# Arduino_Uno_R3_CP.net
KiCad netlist of a schematic drawn in Altium Designer
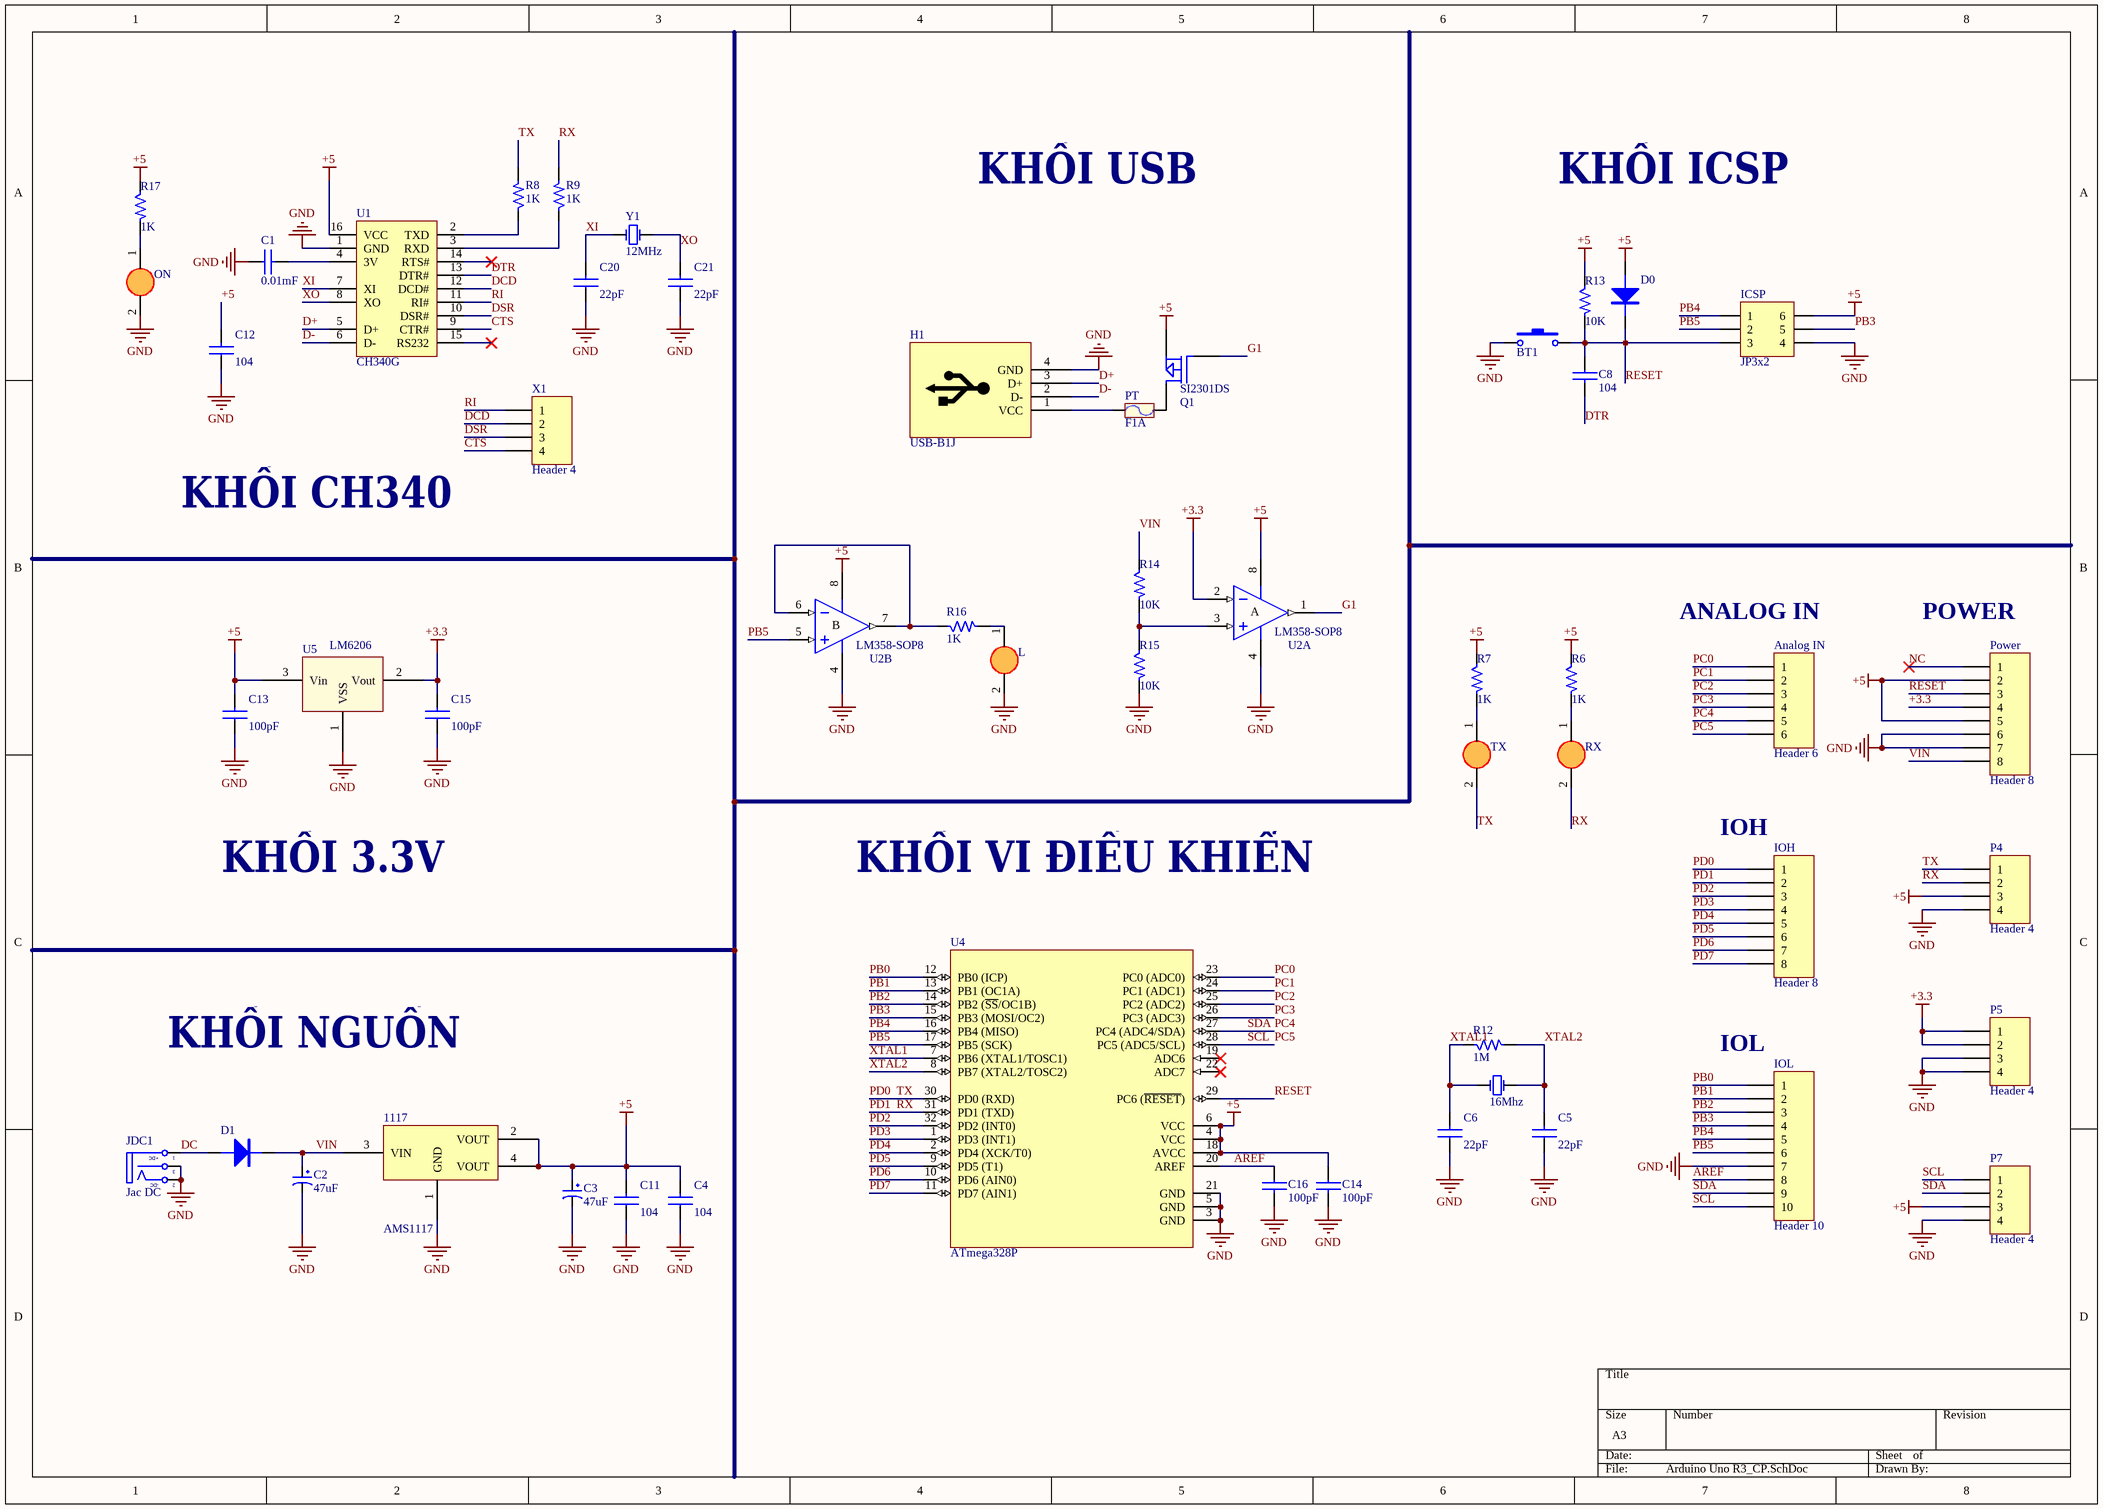
[diagram p0: Arduino Uno R3_CP.SchDoc]

(export (version "E")
  (design (tool "Eeschema 10.0.6"))
  (components
    (comp (ref "1117")
      (value "AMS1117")
      (footprint "SOT223-4N")
      (description "AMS")
      (libsource (lib "Thu Vien Chuan MH") (part "AMS1117"))
    )
    (comp (ref "Analog IN")
      (value "Header 6")
      (footprint "JP6-C1T")
      (description "Header, 6-Pin")
      (fields (field (name "PUBLISHER") "Altium Limited"))
      (libsource (lib "Miscellaneous Connectors") (part "Header 6"))
    )
    (comp (ref "BT1")
      (value "Nut Nhan 2 Chan")
      (footprint "BT 4 PIN 6.2*6.2*3.1")
      (fields (field (name "PUBLISHER") "Altium Limited"))
      (libsource (lib "Thu Vien Chuan MH") (part "Nut Nhan 2 Chan"))
    )
    (comp (ref "C1")
      (value "0.01mF")
      (footprint "CN-SMD-0805")
      (description "Tu 0805")
      (libsource (lib "Thu Vien Chuan MH") (part "Tu 0805"))
    )
    (comp (ref "C2")
      (value "47uF")
      (footprint "CAP-ALU-SMD-5x5.5x1.4")
      (description "Cap P  0,1uF < 22uF , 16 - 50V")
      (libsource (lib "Thu Vien Chuan MH") (part "CP1"))
    )
    (comp (ref "C3")
      (value "47uF")
      (footprint "CAP-ALU-SMD-5x5.5x1.4")
      (description "Cap P  0,1uF < 22uF , 16 - 50V")
      (libsource (lib "Thu Vien Chuan MH") (part "CP1"))
    )
    (comp (ref "C4")
      (value "104")
      (footprint "CN-SMD-0805")
      (description "Tu 0805")
      (libsource (lib "Thu Vien Chuan MH") (part "Tu 0805"))
    )
    (comp (ref "C5")
      (value "22pF")
      (footprint "CN-SMD-0805")
      (description "Tu 0805")
      (libsource (lib "Thu Vien Chuan MH") (part "Tu 0805"))
    )
    (comp (ref "C6")
      (value "22pF")
      (footprint "CN-SMD-0805")
      (description "Tu 0805")
      (libsource (lib "Thu Vien Chuan MH") (part "Tu 0805"))
    )
    (comp (ref "C8")
      (value "104")
      (footprint "CN-SMD-0805")
      (description "Tu 0805")
      (libsource (lib "Thu Vien Chuan MH") (part "Tu 0805"))
    )
    (comp (ref "C11")
      (value "104")
      (footprint "CN-SMD-0805")
      (description "Tu 0805")
      (libsource (lib "Thu Vien Chuan MH") (part "Tu 0805"))
    )
    (comp (ref "C12")
      (value "104")
      (footprint "CN-SMD-0805")
      (description "Tu 0805")
      (libsource (lib "Thu Vien Chuan MH") (part "Tu 0805"))
    )
    (comp (ref "C13")
      (value "100pF")
      (footprint "CN-SMD-0805")
      (description "Tu 0805")
      (libsource (lib "Thu Vien Chuan MH") (part "Tu 0805"))
    )
    (comp (ref "C14")
      (value "100pF")
      (footprint "CN-SMD-0805")
      (description "Tu 0805")
      (libsource (lib "Thu Vien Chuan MH") (part "Tu 0805"))
    )
    (comp (ref "C15")
      (value "100pF")
      (footprint "CN-SMD-0805")
      (description "Tu 0805")
      (libsource (lib "Thu Vien Chuan MH") (part "Tu 0805"))
    )
    (comp (ref "C16")
      (value "100pF")
      (footprint "CN-SMD-0805")
      (description "Tu 0805")
      (libsource (lib "Thu Vien Chuan MH") (part "Tu 0805"))
    )
    (comp (ref "C20")
      (value "22pF")
      (footprint "CN-SMD-0805")
      (description "Tu 0805")
      (libsource (lib "Thu Vien Chuan MH") (part "Tu 0805"))
    )
    (comp (ref "C21")
      (value "22pF")
      (footprint "CN-SMD-0805")
      (description "Tu 0805")
      (libsource (lib "Thu Vien Chuan MH") (part "Tu 0805"))
    )
    (comp (ref "D0")
      (value "~")
      (footprint "RES-SMD-1206")
      (description "Diode SS14 DO214 Schottky 1A 40V ( 1N5819 DO214)")
      (libsource (lib "MH_DA_THU_VIEN_16122016") (part "Diode SS14 DO214 Schottky 1A 40V ( 1N5819 DO214)_MH"))
    )
    (comp (ref "D1")
      (value "~")
      (footprint "SMA")
      (description "Diode SS14 DO214 Schottky 1A 40V ( 1N5819 DO214)")
      (libsource (lib "MH_DA_THU_VIEN_16122016") (part "Diode SS14 DO214 Schottky 1A 40V ( 1N5819 DO214)_MH"))
    )
    (comp (ref "H1")
      (value "USB-B1J")
      (footprint "USB-B-STRANGE")
      (description "USB conector")
      (libsource (lib "Thu Vien Chuan MH") (part "USB"))
    )
    (comp (ref "ICSP")
      (value "JP3x2")
      (footprint "JP3-D2T")
      (description "WR-PHD 2.54 mm Dual Socket Header")
      (fields
        (field (name "MANUFACTURER") "Würth Elektronik eiSos GmbH")
        (field (name "PARTNO") "61300621821")
        (field (name "CREATED BY") "Karrer Zheng")
      )
      (libsource (lib "Thu Vien Chuan MH") (part "JP3x2_3"))
    )
    (comp (ref "IOH")
      (value "Header 8")
      (footprint "JP8-C1T")
      (description "Header, 8-Pin")
      (fields (field (name "PUBLISHER") "Altium Limited"))
      (libsource (lib "Miscellaneous Connectors") (part "Header 8"))
    )
    (comp (ref "IOL")
      (value "Header 10")
      (footprint "JP10-C1T")
      (description "Header, 10-Pin")
      (fields (field (name "PUBLISHER") "Altium Limited"))
      (libsource (lib "Miscellaneous Connectors") (part "Header 10"))
    )
    (comp (ref "JDC1")
      (value "Jac DC")
      (footprint "DC-IN")
      (description "Jac DC input")
      (libsource (lib "Thu Vien Chuan MH") (part "DCIN"))
    )
    (comp (ref "L")
      (value "~")
      (footprint "LED-0805-Red")
      (description "LED 3mm")
      (libsource (lib "MH_DA_THU_VIEN_16122016") (part "LED SMD_0805_MH"))
    )
    (comp (ref "ON")
      (value "~")
      (footprint "LED-0805-Red")
      (description "LED 3mm")
      (libsource (lib "MH_DA_THU_VIEN_16122016") (part "LED SMD_0805_MH"))
    )
    (comp (ref "P4")
      (value "Header 4")
      (footprint "JP4-D1T")
      (description "Header, 4-Pin")
      (fields (field (name "PUBLISHER") "Altium Limited"))
      (libsource (lib "Miscellaneous Connectors") (part "Header 4"))
    )
    (comp (ref "P5")
      (value "Header 4")
      (footprint "JP4-D1T")
      (description "Header, 4-Pin")
      (fields (field (name "PUBLISHER") "Altium Limited"))
      (libsource (lib "Miscellaneous Connectors") (part "Header 4"))
    )
    (comp (ref "P7")
      (value "Header 4")
      (footprint "JP4-D1T")
      (description "Header, 4-Pin")
      (fields (field (name "PUBLISHER") "Altium Limited"))
      (libsource (lib "Miscellaneous Connectors") (part "Header 4"))
    )
    (comp (ref "Power")
      (value "Header 8")
      (footprint "JP8-C1T")
      (description "Header, 8-Pin")
      (fields (field (name "PUBLISHER") "Altium Limited"))
      (libsource (lib "Miscellaneous Connectors") (part "Header 8"))
    )
    (comp (ref "PT")
      (value "F1A")
      (footprint "FUSE-SMD-0805")
      (description "Fuse")
      (fields (field (name "DESIGNED BY") "VanDungEvn"))
      (libsource (lib "Thu Vien Chuan MH") (part "Fuse"))
    )
    (comp (ref "Q1")
      (value "SI2301DS")
      (footprint "SOT23")
      (libsource (lib "Thu Vien Chuan MH") (part "MOSFET P"))
    )
    (comp (ref "R6")
      (value "1K")
      (footprint "RES-SMD-0805")
      (description "Tro 0805")
      (libsource (lib "Thu Vien Chuan MH") (part "Tro 0805"))
    )
    (comp (ref "R7")
      (value "1K")
      (footprint "RES-SMD-0805")
      (description "Tro 0805")
      (libsource (lib "Thu Vien Chuan MH") (part "Tro 0805"))
    )
    (comp (ref "R8")
      (value "1K")
      (footprint "RES-SMD-0805")
      (description "Tro 0805")
      (libsource (lib "Thu Vien Chuan MH") (part "Tro 0805"))
    )
    (comp (ref "R9")
      (value "1K")
      (footprint "RES-SMD-0805")
      (description "Tro 0805")
      (libsource (lib "Thu Vien Chuan MH") (part "Tro 0805"))
    )
    (comp (ref "R12")
      (value "1M")
      (footprint "RES-SMD-0805")
      (description "Tro 0805")
      (libsource (lib "Thu Vien Chuan MH") (part "Tro 0805"))
    )
    (comp (ref "R13")
      (value "10K")
      (footprint "RES-SMD-0805")
      (description "Tro 0805")
      (libsource (lib "Thu Vien Chuan MH") (part "Tro 0805"))
    )
    (comp (ref "R14")
      (value "10K")
      (footprint "RES-SMD-0805")
      (description "Tro 0805")
      (libsource (lib "Thu Vien Chuan MH") (part "Tro 0805"))
    )
    (comp (ref "R15")
      (value "10K")
      (footprint "RES-SMD-0805")
      (description "Tro 0805")
      (libsource (lib "Thu Vien Chuan MH") (part "Tro 0805"))
    )
    (comp (ref "R16")
      (value "1K")
      (footprint "RES-SMD-0805")
      (description "Tro 0805")
      (libsource (lib "Thu Vien Chuan MH") (part "Tro 0805"))
    )
    (comp (ref "R17")
      (value "1K")
      (footprint "RES-SMD-0805")
      (description "Tro 0805")
      (libsource (lib "Thu Vien Chuan MH") (part "Tro 0805"))
    )
    (comp (ref "RX")
      (value "~")
      (footprint "LED-0805-Red")
      (description "LED 3mm")
      (libsource (lib "MH_DA_THU_VIEN_16122016") (part "LED SMD_0805_MH"))
    )
    (comp (ref "TX")
      (value "~")
      (footprint "LED-0805-Red")
      (description "LED 3mm")
      (libsource (lib "MH_DA_THU_VIEN_16122016") (part "LED SMD_0805_MH"))
    )
    (comp (ref "U1")
      (value "CH340G")
      (footprint "SO16")
      (description "High and Low Side Driver")
      (fields (field (name "PUBLISHER") "Altium Limited"))
      (libsource (lib "Thu Vien Chuan MH") (part "CH340G"))
    )
    (comp (ref "U2")
      (value "LM358-SOP8")
      (footprint "SO8")
      (description "Dual Low-Power Operational Amplifier")
      (fields (field (name "PUBLISHER") "Altium Limited"))
      (libsource (lib "Thu Vien Chuan MH") (part "LM358-SOP8"))
    )
    (comp (ref "U4")
      (value "ATmega328P")
      (footprint "TQFP32")
      (description "8-Bit AVR Microcontroller with 8K Bytes of In-System Programmable Flash Memory")
      (fields (field (name "PUBLISHER") "Altium Limited"))
      (libsource (lib "Lib_Chuan_03_08_2013") (part "ATmega8-16AC"))
    )
    (comp (ref "U5")
      (value "LM6206")
      (footprint "SOT23")
      (libsource (lib "Thu Vien Chuan MH") (part "xc6206"))
    )
    (comp (ref "X1")
      (value "Header 4")
      (footprint "HDR1X4")
      (description "Header, 4-Pin")
      (fields (field (name "PUBLISHER") "Altium Limited"))
      (libsource (lib "Miscellaneous Connectors") (part "Header 4"))
    )
    (comp (ref "Y1")
      (value "12MHz")
      (footprint "Thu Vien Chuan MH:XTAL-RU49/4")
      (libsource (lib "Thu Vien Chuan MH") (part "CRYSTAL 12MHz"))
    )
    (comp (ref "Y2")
      (value "16Mhz")
      (footprint "Thu Vien Chuan MH:XTAL-RU49/4")
      (description "Crystal Oscillator")
      (fields (field (name "PUBLISHER") "Altium Limited"))
      (libsource (lib "Thu Vien Chuan MH") (part "Crystal"))
    )
  )
  (nets
    (net (code "1") (name "+3.3") (class "Default")
      (node (ref "C15") (pin "2") (pinfunction "2_2") (pintype "passive"))
      (node (ref "P5") (pin "1") (pinfunction "1_1") (pintype "passive"))
      (node (ref "P5") (pin "2") (pinfunction "2_2") (pintype "passive"))
      (node (ref "Power") (pin "4") (pinfunction "4_4") (pintype "passive"))
      (node (ref "U2") (pin "2") (pinfunction "IN-_2") (pintype "input"))
      (node (ref "U5") (pin "2") (pinfunction "Vout_2") (pintype "passive"))
    )
    (net (code "2") (name "+5") (class "Default")
      (node (ref "1117") (pin "2") (pinfunction "VOUT_2") (pintype "passive"))
      (node (ref "1117") (pin "4") (pinfunction "VOUT_4") (pintype "passive"))
      (node (ref "C11") (pin "2") (pinfunction "2_2") (pintype "passive"))
      (node (ref "C12") (pin "2") (pinfunction "2_2") (pintype "passive"))
      (node (ref "C13") (pin "2") (pinfunction "2_2") (pintype "passive"))
      (node (ref "C14") (pin "1") (pinfunction "1_1") (pintype "passive"))
      (node (ref "C3") (pin "1") (pinfunction "1_1") (pintype "passive"))
      (node (ref "C4") (pin "2") (pinfunction "2_2") (pintype "passive"))
      (node (ref "D0") (pin "1") (pinfunction "1_1") (pintype "passive"))
      (node (ref "ICSP") (pin "6") (pinfunction "6_6") (pintype "passive"))
      (node (ref "P4") (pin "3") (pinfunction "3_3") (pintype "passive"))
      (node (ref "P7") (pin "3") (pinfunction "3_3") (pintype "passive"))
      (node (ref "Power") (pin "2") (pinfunction "2_2") (pintype "passive"))
      (node (ref "Power") (pin "5") (pinfunction "5_5") (pintype "passive"))
      (node (ref "Q1") (pin "3") (pinfunction "S_3") (pintype "passive"))
      (node (ref "R13") (pin "1") (pinfunction "1_1") (pintype "passive"))
      (node (ref "R17") (pin "1") (pinfunction "1_1") (pintype "passive"))
      (node (ref "R6") (pin "1") (pinfunction "1_1") (pintype "passive"))
      (node (ref "R7") (pin "1") (pinfunction "1_1") (pintype "passive"))
      (node (ref "U1") (pin "16") (pinfunction "VCC_16") (pintype "passive"))
      (node (ref "U2") (pin "8") (pinfunction "V+_8") (pintype "power_in"))
      (node (ref "U4") (pin "18") (pinfunction "AVCC_18") (pintype "power_in"))
      (node (ref "U4") (pin "4") (pinfunction "VCC_4") (pintype "power_in"))
      (node (ref "U4") (pin "6") (pinfunction "VCC_6") (pintype "power_in"))
      (node (ref "U5") (pin "3") (pinfunction "Vin_3") (pintype "passive"))
    )
    (net (code "3") (name "/AREF") (class "Default")
      (node (ref "C16") (pin "1") (pinfunction "1_1") (pintype "passive"))
      (node (ref "IOL") (pin "8") (pinfunction "8_8") (pintype "passive"))
      (node (ref "U4") (pin "20") (pinfunction "AREF_20") (pintype "passive"))
    )
    (net (code "4") (name "/CTS") (class "Default")
      (node (ref "U1") (pin "9") (pinfunction "CTR#_9") (pintype "passive"))
      (node (ref "X1") (pin "4") (pinfunction "4_4") (pintype "passive"))
    )
    (net (code "5") (name "/D+") (class "Default")
      (node (ref "H1") (pin "3") (pinfunction "D+_3") (pintype "passive"))
      (node (ref "U1") (pin "5") (pinfunction "D+_5") (pintype "passive"))
    )
    (net (code "6") (name "/D-") (class "Default")
      (node (ref "H1") (pin "2") (pinfunction "D-_2") (pintype "passive"))
      (node (ref "U1") (pin "6") (pinfunction "D-_6") (pintype "passive"))
    )
    (net (code "7") (name "/DC") (class "Default")
      (node (ref "D1") (pin "1") (pinfunction "1_1") (pintype "passive"))
      (node (ref "JDC1") (pin "1") (pinfunction "T_1") (pintype "passive"))
    )
    (net (code "8") (name "/DCD") (class "Default")
      (node (ref "U1") (pin "12") (pinfunction "DCD#_12") (pintype "passive"))
      (node (ref "X1") (pin "2") (pinfunction "2_2") (pintype "passive"))
    )
    (net (code "9") (name "/DSR") (class "Default")
      (node (ref "U1") (pin "10") (pinfunction "DSR#_10") (pintype "passive"))
      (node (ref "X1") (pin "3") (pinfunction "3_3") (pintype "passive"))
    )
    (net (code "10") (name "/DTR") (class "Default")
      (node (ref "C8") (pin "2") (pinfunction "2_2") (pintype "passive"))
      (node (ref "U1") (pin "13") (pinfunction "DTR#_13") (pintype "passive"))
    )
    (net (code "11") (name "/G1") (class "Default")
      (node (ref "Q1") (pin "1") (pinfunction "G_1") (pintype "passive"))
      (node (ref "U2") (pin "1") (pinfunction "OUT_1") (pintype "output"))
    )
    (net (code "12") (name "/NC") (class "Default")
      (node (ref "Power") (pin "1") (pinfunction "1_1") (pintype "passive+no_connect"))
    )
    (net (code "13") (name "/PB0") (class "Default")
      (node (ref "IOL") (pin "1") (pinfunction "1_1") (pintype "passive"))
      (node (ref "U4") (pin "12") (pinfunction "PB0_(ICP)_12") (pintype "bidirectional"))
    )
    (net (code "14") (name "/PB1") (class "Default")
      (node (ref "IOL") (pin "2") (pinfunction "2_2") (pintype "passive"))
      (node (ref "U4") (pin "13") (pinfunction "PB1_(OC1A)_13") (pintype "bidirectional"))
    )
    (net (code "15") (name "/PB2") (class "Default")
      (node (ref "IOL") (pin "3") (pinfunction "3_3") (pintype "passive"))
      (node (ref "U4") (pin "14") (pinfunction "PB2_(~{SS}/OC1B)_14") (pintype "bidirectional"))
    )
    (net (code "16") (name "/PB3") (class "Default")
      (node (ref "ICSP") (pin "5") (pinfunction "5_5") (pintype "passive"))
      (node (ref "IOL") (pin "4") (pinfunction "4_4") (pintype "passive"))
      (node (ref "U4") (pin "15") (pinfunction "PB3_(MOSI/OC2)_15") (pintype "bidirectional"))
    )
    (net (code "17") (name "/PB4") (class "Default")
      (node (ref "ICSP") (pin "1") (pinfunction "1_1") (pintype "passive"))
      (node (ref "IOL") (pin "5") (pinfunction "5_5") (pintype "passive"))
      (node (ref "U4") (pin "16") (pinfunction "PB4_(MISO)_16") (pintype "bidirectional"))
    )
    (net (code "18") (name "/PB5") (class "Default")
      (node (ref "ICSP") (pin "2") (pinfunction "2_2") (pintype "passive"))
      (node (ref "IOL") (pin "6") (pinfunction "6_6") (pintype "passive"))
      (node (ref "U2") (pin "5") (pinfunction "IN+_5") (pintype "input"))
      (node (ref "U4") (pin "17") (pinfunction "PB5_(SCK)_17") (pintype "bidirectional"))
    )
    (net (code "19") (name "/PC0") (class "Default")
      (node (ref "Analog IN") (pin "1") (pinfunction "1_1") (pintype "passive"))
      (node (ref "U4") (pin "23") (pinfunction "PC0_(ADC0)_23") (pintype "bidirectional"))
    )
    (net (code "20") (name "/PC1") (class "Default")
      (node (ref "Analog IN") (pin "2") (pinfunction "2_2") (pintype "passive"))
      (node (ref "U4") (pin "24") (pinfunction "PC1_(ADC1)_24") (pintype "bidirectional"))
    )
    (net (code "21") (name "/PC2") (class "Default")
      (node (ref "Analog IN") (pin "3") (pinfunction "3_3") (pintype "passive"))
      (node (ref "U4") (pin "25") (pinfunction "PC2_(ADC2)_25") (pintype "bidirectional"))
    )
    (net (code "22") (name "/PC3") (class "Default")
      (node (ref "Analog IN") (pin "4") (pinfunction "4_4") (pintype "passive"))
      (node (ref "U4") (pin "26") (pinfunction "PC3_(ADC3)_26") (pintype "bidirectional"))
    )
    (net (code "23") (name "/PC4") (class "Default")
      (node (ref "Analog IN") (pin "5") (pinfunction "5_5") (pintype "passive"))
      (node (ref "IOL") (pin "9") (pinfunction "9_9") (pintype "passive"))
      (node (ref "P7") (pin "2") (pinfunction "2_2") (pintype "passive"))
      (node (ref "U4") (pin "27") (pinfunction "PC4_(ADC4/SDA)_27") (pintype "bidirectional"))
    )
    (net (code "24") (name "/PC5") (class "Default")
      (node (ref "Analog IN") (pin "6") (pinfunction "6_6") (pintype "passive"))
      (node (ref "IOL") (pin "10") (pinfunction "10_10") (pintype "passive"))
      (node (ref "P7") (pin "1") (pinfunction "1_1") (pintype "passive"))
      (node (ref "U4") (pin "28") (pinfunction "PC5_(ADC5/SCL)_28") (pintype "bidirectional"))
    )
    (net (code "25") (name "/PD0") (class "Default")
      (node (ref "IOH") (pin "1") (pinfunction "1_1") (pintype "passive"))
      (node (ref "P4") (pin "1") (pinfunction "1_1") (pintype "passive"))
      (node (ref "R8") (pin "2") (pinfunction "2_2") (pintype "passive"))
      (node (ref "TX") (pin "2") (pinfunction "K_2") (pintype "passive"))
      (node (ref "U4") (pin "30") (pinfunction "PD0_(RXD)_30") (pintype "bidirectional"))
    )
    (net (code "26") (name "/PD1") (class "Default")
      (node (ref "IOH") (pin "2") (pinfunction "2_2") (pintype "passive"))
      (node (ref "P4") (pin "2") (pinfunction "2_2") (pintype "passive"))
      (node (ref "R9") (pin "2") (pinfunction "2_2") (pintype "passive"))
      (node (ref "RX") (pin "2") (pinfunction "K_2") (pintype "passive"))
      (node (ref "U4") (pin "31") (pinfunction "PD1_(TXD)_31") (pintype "bidirectional"))
    )
    (net (code "27") (name "/PD2") (class "Default")
      (node (ref "IOH") (pin "3") (pinfunction "3_3") (pintype "passive"))
      (node (ref "U4") (pin "32") (pinfunction "PD2_(INT0)_32") (pintype "bidirectional"))
    )
    (net (code "28") (name "/PD3") (class "Default")
      (node (ref "IOH") (pin "4") (pinfunction "4_4") (pintype "passive"))
      (node (ref "U4") (pin "1") (pinfunction "PD3_(INT1)_1") (pintype "bidirectional"))
    )
    (net (code "29") (name "/PD4") (class "Default")
      (node (ref "IOH") (pin "5") (pinfunction "5_5") (pintype "passive"))
      (node (ref "U4") (pin "2") (pinfunction "PD4_(XCK/T0)_2") (pintype "bidirectional"))
    )
    (net (code "30") (name "/PD5") (class "Default")
      (node (ref "IOH") (pin "6") (pinfunction "6_6") (pintype "passive"))
      (node (ref "U4") (pin "9") (pinfunction "PD5_(T1)_9") (pintype "bidirectional"))
    )
    (net (code "31") (name "/PD6") (class "Default")
      (node (ref "IOH") (pin "7") (pinfunction "7_7") (pintype "passive"))
      (node (ref "U4") (pin "10") (pinfunction "PD6_(AIN0)_10") (pintype "bidirectional"))
    )
    (net (code "32") (name "/PD7") (class "Default")
      (node (ref "IOH") (pin "8") (pinfunction "8_8") (pintype "passive"))
      (node (ref "U4") (pin "11") (pinfunction "PD7_(AIN1)_11") (pintype "bidirectional"))
    )
    (net (code "33") (name "/RESET") (class "Default")
      (node (ref "BT1") (pin "2") (pinfunction "2_2") (pintype "passive"))
      (node (ref "C8") (pin "1") (pinfunction "1_1") (pintype "passive"))
      (node (ref "D0") (pin "2") (pinfunction "2_2") (pintype "passive"))
      (node (ref "ICSP") (pin "3") (pinfunction "3_3") (pintype "passive"))
      (node (ref "Power") (pin "3") (pinfunction "3_3") (pintype "passive"))
      (node (ref "R13") (pin "2") (pinfunction "2_2") (pintype "passive"))
      (node (ref "U4") (pin "29") (pinfunction "PC6_(~{RESET})_29") (pintype "bidirectional"))
    )
    (net (code "34") (name "/RI") (class "Default")
      (node (ref "U1") (pin "11") (pinfunction "RI#_11") (pintype "passive"))
      (node (ref "X1") (pin "1") (pinfunction "1_1") (pintype "passive"))
    )
    (net (code "35") (name "/VIN") (class "Default")
      (node (ref "1117") (pin "3") (pinfunction "VIN_3") (pintype "passive"))
      (node (ref "C2") (pin "1") (pinfunction "1_1") (pintype "passive"))
      (node (ref "D1") (pin "2") (pinfunction "2_2") (pintype "passive"))
      (node (ref "Power") (pin "8") (pinfunction "8_8") (pintype "passive"))
      (node (ref "R14") (pin "1") (pinfunction "1_1") (pintype "passive"))
    )
    (net (code "36") (name "/XI") (class "Default")
      (node (ref "C20") (pin "2") (pinfunction "2_2") (pintype "passive"))
      (node (ref "U1") (pin "7") (pinfunction "XI_7") (pintype "passive"))
      (node (ref "Y1") (pin "1") (pinfunction "OSC1_1") (pintype "passive"))
    )
    (net (code "37") (name "/XO") (class "Default")
      (node (ref "C21") (pin "2") (pinfunction "2_2") (pintype "passive"))
      (node (ref "U1") (pin "8") (pinfunction "XO_8") (pintype "passive"))
      (node (ref "Y1") (pin "2") (pinfunction "OSC2_2") (pintype "passive"))
    )
    (net (code "38") (name "/XTAL1") (class "Default")
      (node (ref "C6") (pin "2") (pinfunction "2_2") (pintype "passive"))
      (node (ref "R12") (pin "1") (pinfunction "1_1") (pintype "passive"))
      (node (ref "U4") (pin "7") (pinfunction "PB6_(XTAL1/TOSC1)_7") (pintype "bidirectional"))
      (node (ref "Y2") (pin "1") (pinfunction "OSC1_1") (pintype "passive"))
    )
    (net (code "39") (name "/XTAL2") (class "Default")
      (node (ref "C5") (pin "2") (pinfunction "2_2") (pintype "passive"))
      (node (ref "R12") (pin "2") (pinfunction "2_2") (pintype "passive"))
      (node (ref "U4") (pin "8") (pinfunction "PB7_(XTAL2/TOSC2)_8") (pintype "bidirectional"))
      (node (ref "Y2") (pin "2") (pinfunction "OSC2_2") (pintype "passive"))
    )
    (net (code "40") (name "GND") (class "Default")
      (node (ref "1117") (pin "1") (pinfunction "GND_1") (pintype "passive"))
      (node (ref "BT1") (pin "1") (pinfunction "1_1") (pintype "passive"))
      (node (ref "C1") (pin "1") (pinfunction "1_1") (pintype "passive"))
      (node (ref "C11") (pin "1") (pinfunction "1_1") (pintype "passive"))
      (node (ref "C12") (pin "1") (pinfunction "1_1") (pintype "passive"))
      (node (ref "C13") (pin "1") (pinfunction "1_1") (pintype "passive"))
      (node (ref "C14") (pin "2") (pinfunction "2_2") (pintype "passive"))
      (node (ref "C15") (pin "1") (pinfunction "1_1") (pintype "passive"))
      (node (ref "C16") (pin "2") (pinfunction "2_2") (pintype "passive"))
      (node (ref "C2") (pin "2") (pinfunction "2_2") (pintype "passive"))
      (node (ref "C20") (pin "1") (pinfunction "1_1") (pintype "passive"))
      (node (ref "C21") (pin "1") (pinfunction "1_1") (pintype "passive"))
      (node (ref "C3") (pin "2") (pinfunction "2_2") (pintype "passive"))
      (node (ref "C4") (pin "1") (pinfunction "1_1") (pintype "passive"))
      (node (ref "C5") (pin "1") (pinfunction "1_1") (pintype "passive"))
      (node (ref "C6") (pin "1") (pinfunction "1_1") (pintype "passive"))
      (node (ref "H1") (pin "4") (pinfunction "GND_4") (pintype "passive"))
      (node (ref "ICSP") (pin "4") (pinfunction "4_4") (pintype "passive"))
      (node (ref "IOL") (pin "7") (pinfunction "7_7") (pintype "passive"))
      (node (ref "JDC1") (pin "2") (pinfunction "TN_2") (pintype "passive"))
      (node (ref "JDC1") (pin "3") (pinfunction "S_3") (pintype "power_in"))
      (node (ref "L") (pin "2") (pinfunction "K_2") (pintype "passive"))
      (node (ref "ON") (pin "2") (pinfunction "K_2") (pintype "passive"))
      (node (ref "P4") (pin "4") (pinfunction "4_4") (pintype "passive"))
      (node (ref "P5") (pin "3") (pinfunction "3_3") (pintype "passive"))
      (node (ref "P5") (pin "4") (pinfunction "4_4") (pintype "passive"))
      (node (ref "P7") (pin "4") (pinfunction "4_4") (pintype "passive"))
      (node (ref "Power") (pin "6") (pinfunction "6_6") (pintype "passive"))
      (node (ref "Power") (pin "7") (pinfunction "7_7") (pintype "passive"))
      (node (ref "R15") (pin "2") (pinfunction "2_2") (pintype "passive"))
      (node (ref "U1") (pin "1") (pinfunction "GND_1") (pintype "passive"))
      (node (ref "U2") (pin "4") (pinfunction "V-_4") (pintype "power_in"))
      (node (ref "U4") (pin "21") (pinfunction "GND_21") (pintype "power_in"))
      (node (ref "U4") (pin "3") (pinfunction "GND_3") (pintype "power_in"))
      (node (ref "U4") (pin "5") (pinfunction "GND_5") (pintype "power_in"))
      (node (ref "U5") (pin "1") (pinfunction "VSS_1") (pintype "passive"))
    )
    (net (code "41") (name "Net-(H1-VCC)") (class "Default")
      (node (ref "H1") (pin "1") (pinfunction "VCC_1") (pintype "passive"))
      (node (ref "PT") (pin "1") (pinfunction "1_1") (pintype "passive"))
    )
    (net (code "42") (name "Net-(L-A)") (class "Default")
      (node (ref "L") (pin "1") (pinfunction "A_1") (pintype "passive"))
      (node (ref "R16") (pin "2") (pinfunction "2_2") (pintype "passive"))
    )
    (net (code "43") (name "Net-(ON-A)") (class "Default")
      (node (ref "ON") (pin "1") (pinfunction "A_1") (pintype "passive"))
      (node (ref "R17") (pin "2") (pinfunction "2_2") (pintype "passive"))
    )
    (net (code "44") (name "Net-(Q1-D)") (class "Default")
      (node (ref "PT") (pin "2") (pinfunction "2_2") (pintype "passive"))
      (node (ref "Q1") (pin "2") (pinfunction "D_2") (pintype "passive"))
    )
    (net (code "45") (name "Net-(RX-A)") (class "Default")
      (node (ref "R6") (pin "2") (pinfunction "2_2") (pintype "passive"))
      (node (ref "RX") (pin "1") (pinfunction "A_1") (pintype "passive"))
    )
    (net (code "46") (name "Net-(TX-A)") (class "Default")
      (node (ref "R7") (pin "2") (pinfunction "2_2") (pintype "passive"))
      (node (ref "TX") (pin "1") (pinfunction "A_1") (pintype "passive"))
    )
    (net (code "47") (name "Net-(U1-3V)") (class "Default")
      (node (ref "C1") (pin "2") (pinfunction "2_2") (pintype "passive"))
      (node (ref "U1") (pin "4") (pinfunction "3V_4") (pintype "passive"))
    )
    (net (code "48") (name "Net-(U1-RXD)") (class "Default")
      (node (ref "R9") (pin "1") (pinfunction "1_1") (pintype "passive"))
      (node (ref "U1") (pin "3") (pinfunction "RXD_3") (pintype "passive"))
    )
    (net (code "49") (name "Net-(U1-TXD)") (class "Default")
      (node (ref "R8") (pin "1") (pinfunction "1_1") (pintype "passive"))
      (node (ref "U1") (pin "2") (pinfunction "TXD_2") (pintype "passive"))
    )
    (net (code "50") (name "Net-(U2A-IN+)") (class "Default")
      (node (ref "R14") (pin "2") (pinfunction "2_2") (pintype "passive"))
      (node (ref "R15") (pin "1") (pinfunction "1_1") (pintype "passive"))
      (node (ref "U2") (pin "3") (pinfunction "IN+_3") (pintype "input"))
    )
    (net (code "51") (name "Net-(U2B-IN-)") (class "Default")
      (node (ref "R16") (pin "1") (pinfunction "1_1") (pintype "passive"))
      (node (ref "U2") (pin "6") (pinfunction "IN-_6") (pintype "input"))
      (node (ref "U2") (pin "7") (pinfunction "OUT_7") (pintype "output"))
    )
    (net (code "52") (name "unconnected-(H1-Pad5)") (class "Default")
      (node (ref "H1") (pin "5") (pinfunction "5_5") (pintype "passive"))
    )
    (net (code "53") (name "unconnected-(H1-Pad6)") (class "Default")
      (node (ref "H1") (pin "6") (pinfunction "6_6") (pintype "passive"))
    )
    (net (code "54") (name "unconnected-(U1-RS232-Pad15)") (class "Default")
      (node (ref "U1") (pin "15") (pinfunction "RS232_15") (pintype "passive+no_connect"))
    )
    (net (code "55") (name "unconnected-(U1-RTS#-Pad14)") (class "Default")
      (node (ref "U1") (pin "14") (pinfunction "RTS#_14") (pintype "passive+no_connect"))
    )
    (net (code "56") (name "unconnected-(U4-ADC6-Pad19)") (class "Default")
      (node (ref "U4") (pin "19") (pinfunction "ADC6_19") (pintype "input+no_connect"))
    )
    (net (code "57") (name "unconnected-(U4-ADC7-Pad22)") (class "Default")
      (node (ref "U4") (pin "22") (pinfunction "ADC7_22") (pintype "input+no_connect"))
    )
  )
)
